# PCB_Schaltplan.net
KiCad netlist of a schematic drawn in EasyEDA
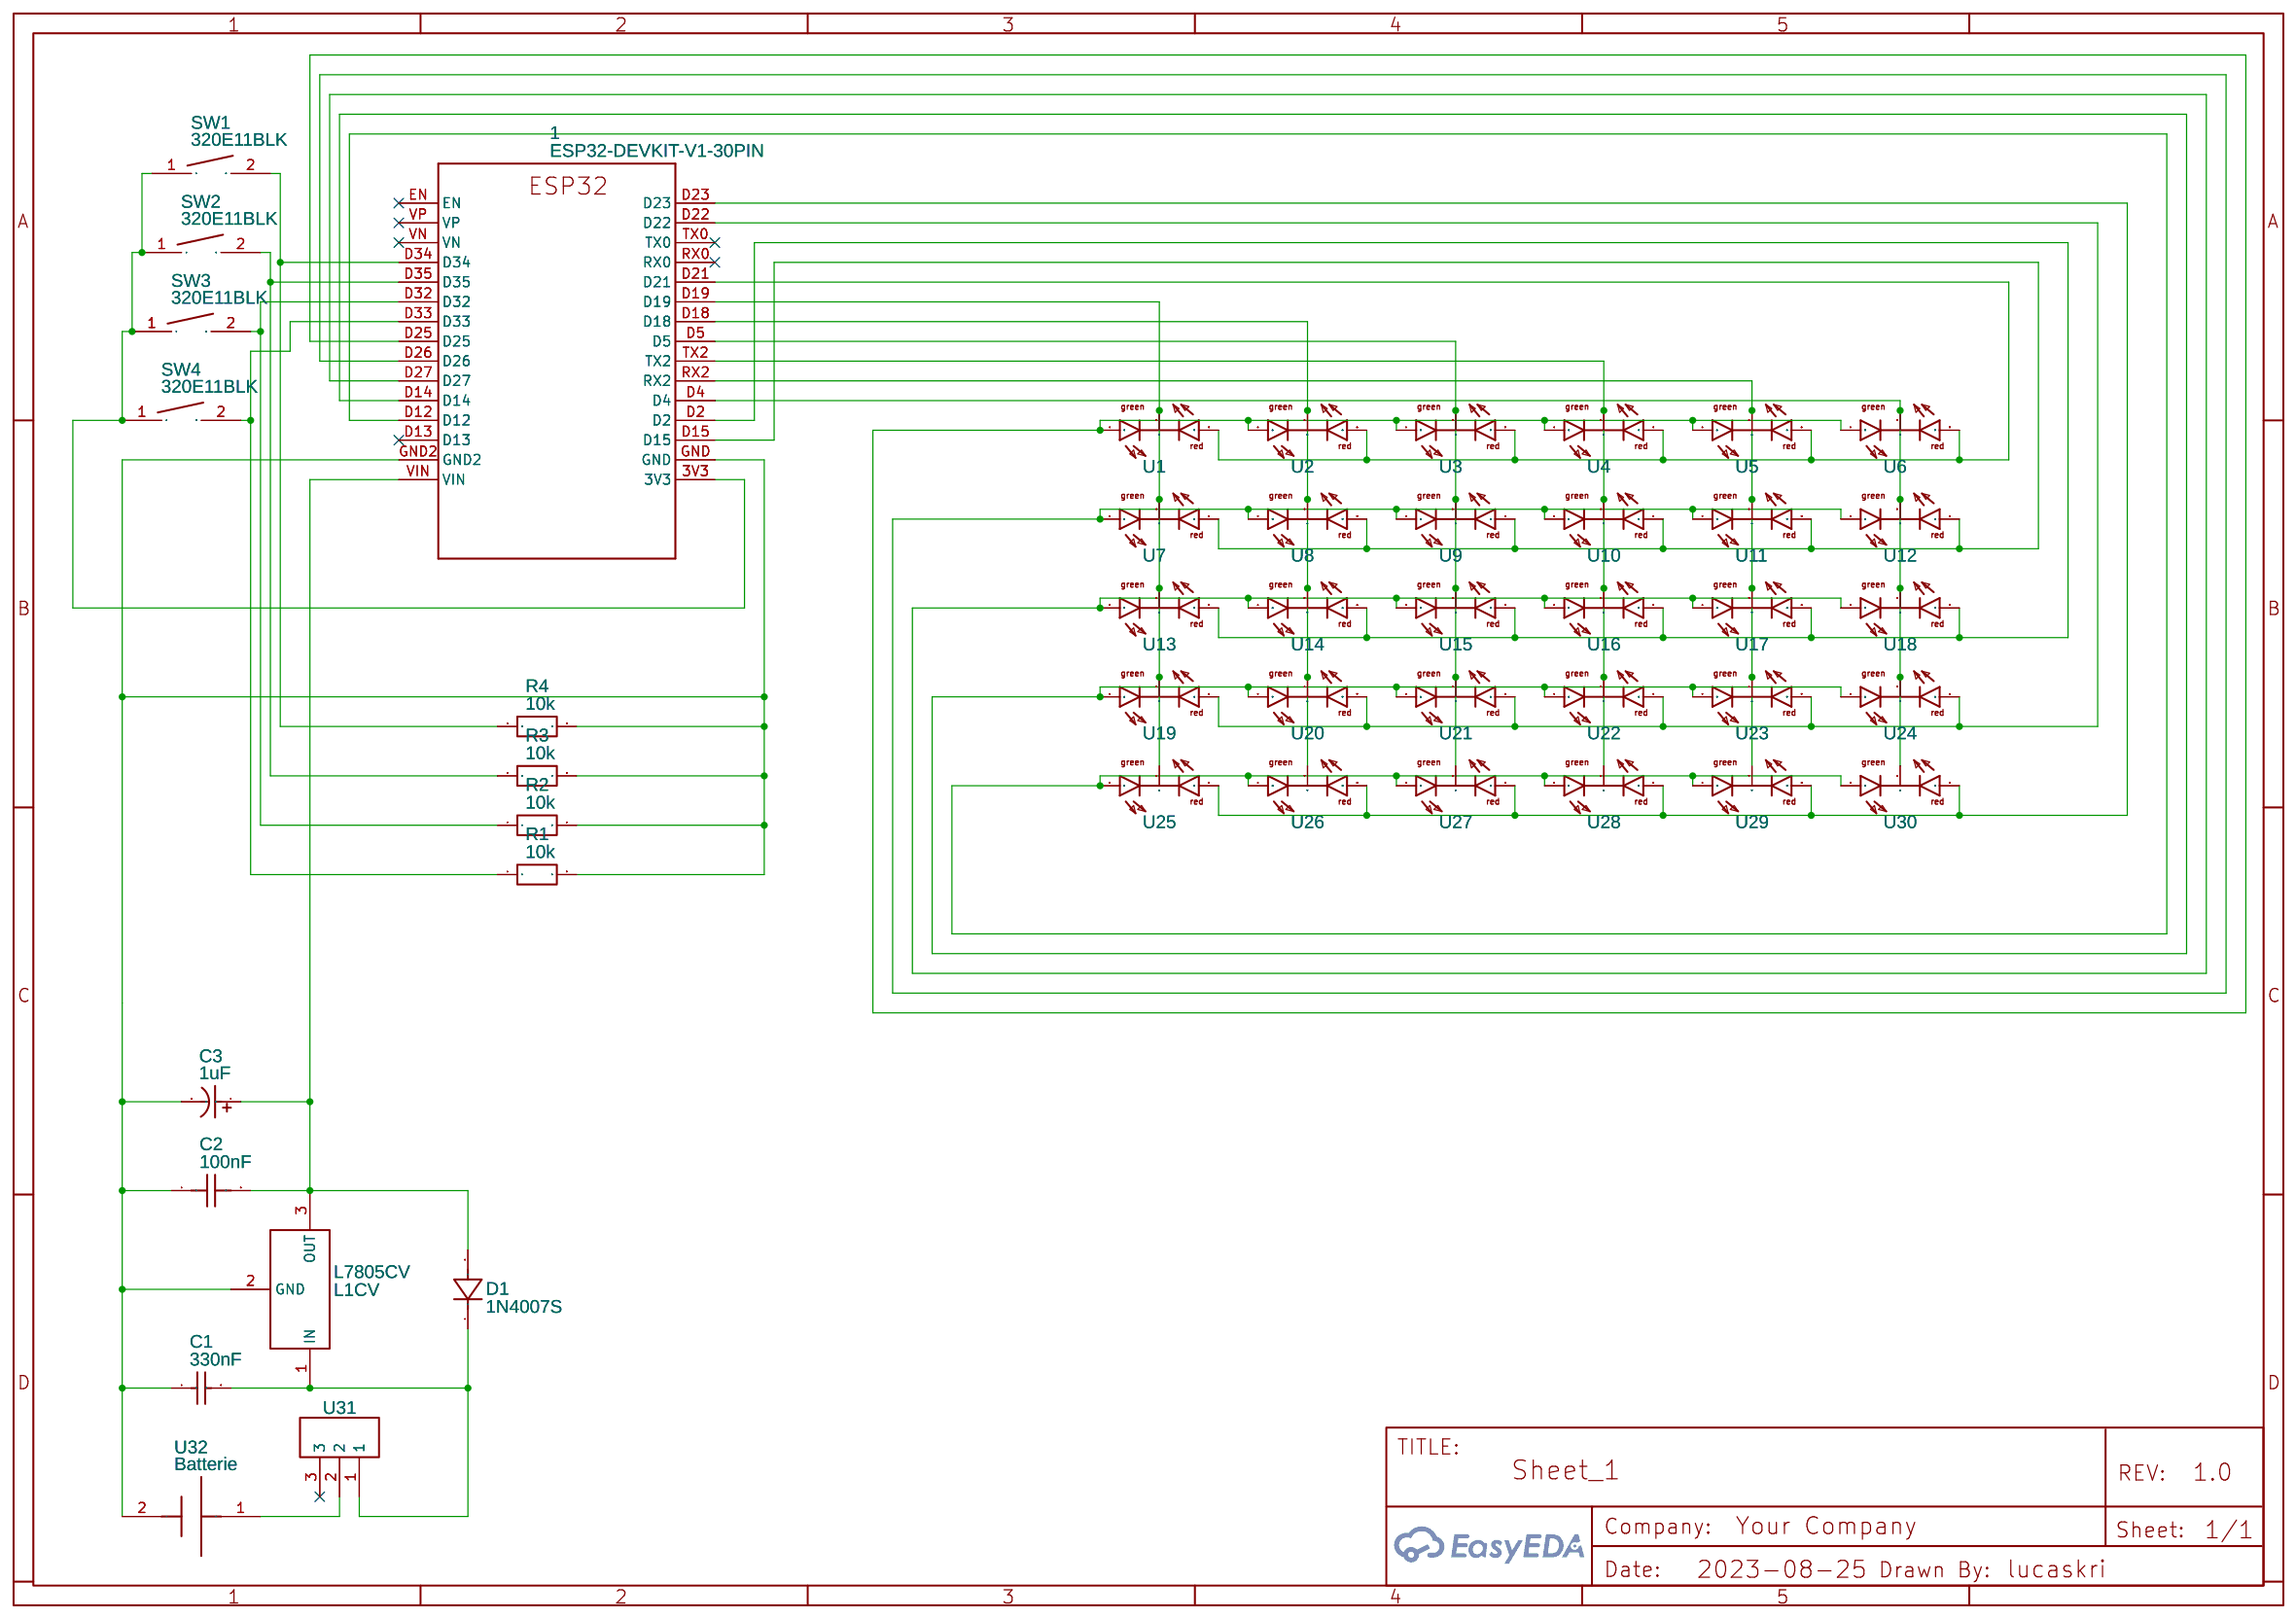
[diagram p0: schematic sheet]

(export (version "E")
  (design (tool "Eeschema 10.0.6"))
  (components
    (comp (ref "1") (value "ESP32-DEVKIT-V1-30PIN") (libsource (lib "") (part "ESP32-DEVKIT-V1-30PIN")))
    (comp (ref "C1")
      (value "330nF")
      (fields (field (name "Manufacturer Part") "CT4-1206Y334M500PF3") (field (name "Manufacturer") "FH(风华)"))
      (libsource (lib "") (part "CT4-1206Y334M500PF3"))
    )
    (comp (ref "C2")
      (value "100nF")
      (fields (field (name "Manufacturer Part") "B32529C0104M289") (field (name "Manufacturer") "TDK"))
      (libsource (lib "") (part "B32529C0104M289"))
    )
    (comp (ref "C3")
      (value "1uF")
      (fields
        (field (name "Manufacturer Part") "KF105M050C05RR0VH2FP0")
        (field (name "Manufacturer") "CX(承兴)")
      )
      (libsource (lib "") (part "1uF 50V 4*5"))
    )
    (comp (ref "D1")
      (value "1N4007S")
      (fields (field (name "Manufacturer") "星海"))
      (libsource (lib "") (part "1N4007S"))
    )
    (comp (ref "L1CV")
      (value "L7805CV")
      (fields (field (name "Manufacturer") "STMicroelectronics"))
      (libsource (lib "") (part "L7805CV"))
    )
    (comp (ref "R1") (value "10k") (libsource (lib "") (part "R_AXIAL-0.3_EU")))
    (comp (ref "R2") (value "10k") (libsource (lib "") (part "R_AXIAL-0.3_EU")))
    (comp (ref "R3") (value "10k") (libsource (lib "") (part "R_AXIAL-0.3_EU")))
    (comp (ref "R4") (value "10k") (libsource (lib "") (part "R_AXIAL-0.3_EU")))
    (comp (ref "SW1")
      (value "320E11BLK")
      (fields (field (name "Manufacturer") "E-Switch"))
      (libsource (lib "") (part "320E11BLK"))
    )
    (comp (ref "SW2")
      (value "320E11BLK")
      (fields (field (name "Manufacturer") "E-Switch"))
      (libsource (lib "") (part "320E11BLK"))
    )
    (comp (ref "SW3")
      (value "320E11BLK")
      (fields (field (name "Manufacturer") "E-Switch"))
      (libsource (lib "") (part "320E11BLK"))
    )
    (comp (ref "SW4")
      (value "320E11BLK")
      (fields (field (name "Manufacturer") "E-Switch"))
      (libsource (lib "") (part "320E11BLK"))
    )
    (comp (ref "U1") (value "NO") (libsource (lib "") (part "DUOLED-RG-C")))
    (comp (ref "U2") (value "NO") (libsource (lib "") (part "DUOLED-RG-C")))
    (comp (ref "U3") (value "NO") (libsource (lib "") (part "DUOLED-RG-C")))
    (comp (ref "U4") (value "NO") (libsource (lib "") (part "DUOLED-RG-C")))
    (comp (ref "U5") (value "NO") (libsource (lib "") (part "DUOLED-RG-C")))
    (comp (ref "U6") (value "NO") (libsource (lib "") (part "DUOLED-RG-C")))
    (comp (ref "U7") (value "NO") (libsource (lib "") (part "DUOLED-RG-C")))
    (comp (ref "U8") (value "NO") (libsource (lib "") (part "DUOLED-RG-C")))
    (comp (ref "U9") (value "NO") (libsource (lib "") (part "DUOLED-RG-C")))
    (comp (ref "U10") (value "NO") (libsource (lib "") (part "DUOLED-RG-C")))
    (comp (ref "U11") (value "NO") (libsource (lib "") (part "DUOLED-RG-C")))
    (comp (ref "U12") (value "NO") (libsource (lib "") (part "DUOLED-RG-C")))
    (comp (ref "U13") (value "NO") (libsource (lib "") (part "DUOLED-RG-C")))
    (comp (ref "U14") (value "NO") (libsource (lib "") (part "DUOLED-RG-C")))
    (comp (ref "U15") (value "NO") (libsource (lib "") (part "DUOLED-RG-C")))
    (comp (ref "U16") (value "NO") (libsource (lib "") (part "DUOLED-RG-C")))
    (comp (ref "U17") (value "NO") (libsource (lib "") (part "DUOLED-RG-C")))
    (comp (ref "U18") (value "NO") (libsource (lib "") (part "DUOLED-RG-C")))
    (comp (ref "U19") (value "NO") (libsource (lib "") (part "DUOLED-RG-C")))
    (comp (ref "U20") (value "NO") (libsource (lib "") (part "DUOLED-RG-C")))
    (comp (ref "U21") (value "NO") (libsource (lib "") (part "DUOLED-RG-C")))
    (comp (ref "U22") (value "NO") (libsource (lib "") (part "DUOLED-RG-C")))
    (comp (ref "U23") (value "NO") (libsource (lib "") (part "DUOLED-RG-C")))
    (comp (ref "U24") (value "NO") (libsource (lib "") (part "DUOLED-RG-C")))
    (comp (ref "U25") (value "NO") (libsource (lib "") (part "DUOLED-RG-C")))
    (comp (ref "U26") (value "NO") (libsource (lib "") (part "DUOLED-RG-C")))
    (comp (ref "U27") (value "NO") (libsource (lib "") (part "DUOLED-RG-C")))
    (comp (ref "U28") (value "NO") (libsource (lib "") (part "DUOLED-RG-C")))
    (comp (ref "U29") (value "NO") (libsource (lib "") (part "DUOLED-RG-C")))
    (comp (ref "U30") (value "NO") (libsource (lib "") (part "DUOLED-RG-C")))
    (comp (ref "U31") (value "NO") (libsource (lib "") (part "CSS-1201")))
    (comp (ref "U32") (value "Batterie") (libsource (lib "") (part "Batterie")))
  )
  (nets
    (net (code "1") (name "Net-(1-Pad3V3)") (class "Default")
      (node (ref "1") (pin "3V3") (pinfunction "3V3_3V3") (pintype "unspecified"))
      (node (ref "SW1") (pin "1") (pinfunction "1_1") (pintype "input"))
      (node (ref "SW2") (pin "1") (pinfunction "1_1") (pintype "input"))
      (node (ref "SW3") (pin "1") (pinfunction "1_1") (pintype "input"))
      (node (ref "SW4") (pin "1") (pinfunction "1_1") (pintype "input"))
    )
    (net (code "2") (name "Net-(1-PadD2)") (class "Default")
      (node (ref "1") (pin "D2") (pinfunction "D2_D2") (pintype "unspecified"))
      (node (ref "U13") (pin "AR") (pinfunction "AR_AR") (pintype "bidirectional"))
      (node (ref "U14") (pin "AR") (pinfunction "AR_AR") (pintype "bidirectional"))
      (node (ref "U15") (pin "AR") (pinfunction "AR_AR") (pintype "bidirectional"))
      (node (ref "U16") (pin "AR") (pinfunction "AR_AR") (pintype "bidirectional"))
      (node (ref "U17") (pin "AR") (pinfunction "AR_AR") (pintype "bidirectional"))
      (node (ref "U18") (pin "AR") (pinfunction "AR_AR") (pintype "bidirectional"))
    )
    (net (code "3") (name "Net-(1-PadD4)") (class "Default")
      (node (ref "1") (pin "D4") (pinfunction "D4_D4") (pintype "unspecified"))
      (node (ref "U12") (pin "C") (pinfunction "C_C") (pintype "bidirectional"))
      (node (ref "U18") (pin "C") (pinfunction "C_C") (pintype "bidirectional"))
      (node (ref "U24") (pin "C") (pinfunction "C_C") (pintype "bidirectional"))
      (node (ref "U30") (pin "C") (pinfunction "C_C") (pintype "bidirectional"))
      (node (ref "U6") (pin "C") (pinfunction "C_C") (pintype "bidirectional"))
    )
    (net (code "4") (name "Net-(1-PadD5)") (class "Default")
      (node (ref "1") (pin "D5") (pinfunction "D5_D5") (pintype "unspecified"))
      (node (ref "U15") (pin "C") (pinfunction "C_C") (pintype "bidirectional"))
      (node (ref "U21") (pin "C") (pinfunction "C_C") (pintype "bidirectional"))
      (node (ref "U27") (pin "C") (pinfunction "C_C") (pintype "bidirectional"))
      (node (ref "U3") (pin "C") (pinfunction "C_C") (pintype "bidirectional"))
      (node (ref "U9") (pin "C") (pinfunction "C_C") (pintype "bidirectional"))
    )
    (net (code "5") (name "Net-(1-PadD15)") (class "Default")
      (node (ref "1") (pin "D15") (pinfunction "D15_D15") (pintype "unspecified"))
      (node (ref "U10") (pin "AR") (pinfunction "AR_AR") (pintype "bidirectional"))
      (node (ref "U11") (pin "AR") (pinfunction "AR_AR") (pintype "bidirectional"))
      (node (ref "U12") (pin "AR") (pinfunction "AR_AR") (pintype "bidirectional"))
      (node (ref "U7") (pin "AR") (pinfunction "AR_AR") (pintype "bidirectional"))
      (node (ref "U8") (pin "AR") (pinfunction "AR_AR") (pintype "bidirectional"))
      (node (ref "U9") (pin "AR") (pinfunction "AR_AR") (pintype "bidirectional"))
    )
    (net (code "6") (name "Net-(1-PadD18)") (class "Default")
      (node (ref "1") (pin "D18") (pinfunction "D18_D18") (pintype "unspecified"))
      (node (ref "U14") (pin "C") (pinfunction "C_C") (pintype "bidirectional"))
      (node (ref "U2") (pin "C") (pinfunction "C_C") (pintype "bidirectional"))
      (node (ref "U20") (pin "C") (pinfunction "C_C") (pintype "bidirectional"))
      (node (ref "U26") (pin "C") (pinfunction "C_C") (pintype "bidirectional"))
      (node (ref "U8") (pin "C") (pinfunction "C_C") (pintype "bidirectional"))
    )
    (net (code "7") (name "Net-(1-PadD19)") (class "Default")
      (node (ref "1") (pin "D19") (pinfunction "D19_D19") (pintype "unspecified"))
      (node (ref "U1") (pin "C") (pinfunction "C_C") (pintype "bidirectional"))
      (node (ref "U13") (pin "C") (pinfunction "C_C") (pintype "bidirectional"))
      (node (ref "U19") (pin "C") (pinfunction "C_C") (pintype "bidirectional"))
      (node (ref "U25") (pin "C") (pinfunction "C_C") (pintype "bidirectional"))
      (node (ref "U7") (pin "C") (pinfunction "C_C") (pintype "bidirectional"))
    )
    (net (code "8") (name "Net-(1-PadD21)") (class "Default")
      (node (ref "1") (pin "D21") (pinfunction "D21_D21") (pintype "unspecified"))
      (node (ref "U1") (pin "AR") (pinfunction "AR_AR") (pintype "bidirectional"))
      (node (ref "U2") (pin "AR") (pinfunction "AR_AR") (pintype "bidirectional"))
      (node (ref "U3") (pin "AR") (pinfunction "AR_AR") (pintype "bidirectional"))
      (node (ref "U4") (pin "AR") (pinfunction "AR_AR") (pintype "bidirectional"))
      (node (ref "U5") (pin "AR") (pinfunction "AR_AR") (pintype "bidirectional"))
      (node (ref "U6") (pin "AR") (pinfunction "AR_AR") (pintype "bidirectional"))
    )
    (net (code "9") (name "Net-(1-PadD22)") (class "Default")
      (node (ref "1") (pin "D22") (pinfunction "D22_D22") (pintype "unspecified"))
      (node (ref "U19") (pin "AR") (pinfunction "AR_AR") (pintype "bidirectional"))
      (node (ref "U20") (pin "AR") (pinfunction "AR_AR") (pintype "bidirectional"))
      (node (ref "U21") (pin "AR") (pinfunction "AR_AR") (pintype "bidirectional"))
      (node (ref "U22") (pin "AR") (pinfunction "AR_AR") (pintype "bidirectional"))
      (node (ref "U23") (pin "AR") (pinfunction "AR_AR") (pintype "bidirectional"))
      (node (ref "U24") (pin "AR") (pinfunction "AR_AR") (pintype "bidirectional"))
    )
    (net (code "10") (name "Net-(1-PadD23)") (class "Default")
      (node (ref "1") (pin "D23") (pinfunction "D23_D23") (pintype "unspecified"))
      (node (ref "U25") (pin "AR") (pinfunction "AR_AR") (pintype "bidirectional"))
      (node (ref "U26") (pin "AR") (pinfunction "AR_AR") (pintype "bidirectional"))
      (node (ref "U27") (pin "AR") (pinfunction "AR_AR") (pintype "bidirectional"))
      (node (ref "U28") (pin "AR") (pinfunction "AR_AR") (pintype "bidirectional"))
      (node (ref "U29") (pin "AR") (pinfunction "AR_AR") (pintype "bidirectional"))
      (node (ref "U30") (pin "AR") (pinfunction "AR_AR") (pintype "bidirectional"))
    )
    (net (code "11") (name "Net-(1-PadD32)") (class "Default")
      (node (ref "1") (pin "D32") (pinfunction "D32_D32") (pintype "unspecified"))
      (node (ref "R2") (pin "1") (pinfunction "1_1") (pintype "unspecified"))
      (node (ref "SW3") (pin "2") (pinfunction "2_2") (pintype "input"))
    )
    (net (code "12") (name "Net-(1-PadD33)") (class "Default")
      (node (ref "1") (pin "D33") (pinfunction "D33_D33") (pintype "unspecified"))
      (node (ref "R1") (pin "1") (pinfunction "1_1") (pintype "unspecified"))
      (node (ref "SW4") (pin "2") (pinfunction "2_2") (pintype "input"))
    )
    (net (code "13") (name "Net-(1-PadD34)") (class "Default")
      (node (ref "1") (pin "D34") (pinfunction "D34_D34") (pintype "unspecified"))
      (node (ref "R4") (pin "1") (pinfunction "1_1") (pintype "unspecified"))
      (node (ref "SW1") (pin "2") (pinfunction "2_2") (pintype "input"))
    )
    (net (code "14") (name "Net-(1-PadD35)") (class "Default")
      (node (ref "1") (pin "D35") (pinfunction "D35_D35") (pintype "unspecified"))
      (node (ref "R3") (pin "1") (pinfunction "1_1") (pintype "unspecified"))
      (node (ref "SW2") (pin "2") (pinfunction "2_2") (pintype "input"))
    )
    (net (code "15") (name "Net-(1-PadRX2)") (class "Default")
      (node (ref "1") (pin "RX2") (pinfunction "RX2_RX2") (pintype "unspecified"))
      (node (ref "U11") (pin "C") (pinfunction "C_C") (pintype "bidirectional"))
      (node (ref "U17") (pin "C") (pinfunction "C_C") (pintype "bidirectional"))
      (node (ref "U23") (pin "C") (pinfunction "C_C") (pintype "bidirectional"))
      (node (ref "U29") (pin "C") (pinfunction "C_C") (pintype "bidirectional"))
      (node (ref "U5") (pin "C") (pinfunction "C_C") (pintype "bidirectional"))
    )
    (net (code "16") (name "Net-(1-PadTX2)") (class "Default")
      (node (ref "1") (pin "TX2") (pinfunction "TX2_TX2") (pintype "unspecified"))
      (node (ref "U10") (pin "C") (pinfunction "C_C") (pintype "bidirectional"))
      (node (ref "U16") (pin "C") (pinfunction "C_C") (pintype "bidirectional"))
      (node (ref "U22") (pin "C") (pinfunction "C_C") (pintype "bidirectional"))
      (node (ref "U28") (pin "C") (pinfunction "C_C") (pintype "bidirectional"))
      (node (ref "U4") (pin "C") (pinfunction "C_C") (pintype "bidirectional"))
    )
    (net (code "17") (name "Net-(D1-A)") (class "Default")
      (node (ref "1") (pin "VIN") (pinfunction "VIN_VIN") (pintype "unspecified"))
      (node (ref "C2") (pin "2") (pinfunction "2_2") (pintype "unspecified"))
      (node (ref "C3") (pin "1") (pinfunction "1_1") (pintype "input"))
      (node (ref "D1") (pin "2") (pinfunction "A_2") (pintype "unspecified"))
      (node (ref "L1CV") (pin "3") (pinfunction "OUT_3") (pintype "unspecified"))
    )
    (net (code "18") (name "Net-(D1-K)") (class "Default")
      (node (ref "C1") (pin "2") (pinfunction "2_2") (pintype "input"))
      (node (ref "D1") (pin "1") (pinfunction "K_1") (pintype "unspecified"))
      (node (ref "L1CV") (pin "1") (pinfunction "IN_1") (pintype "unspecified"))
      (node (ref "U31") (pin "1") (pinfunction "1_1") (pintype "unspecified"))
    )
    (net (code "19") (name "Net-(L1CV-GND)") (class "Default")
      (node (ref "1") (pin "GND") (pinfunction "GND_GND") (pintype "unspecified"))
      (node (ref "1") (pin "GND2") (pinfunction "GND2_GND2") (pintype "unspecified"))
      (node (ref "C1") (pin "1") (pinfunction "1_1") (pintype "input"))
      (node (ref "C2") (pin "1") (pinfunction "1_1") (pintype "unspecified"))
      (node (ref "C3") (pin "2") (pinfunction "2_2") (pintype "input"))
      (node (ref "L1CV") (pin "2") (pinfunction "GND_2") (pintype "unspecified"))
      (node (ref "R1") (pin "2") (pinfunction "2_2") (pintype "unspecified"))
      (node (ref "R2") (pin "2") (pinfunction "2_2") (pintype "unspecified"))
      (node (ref "R3") (pin "2") (pinfunction "2_2") (pintype "unspecified"))
      (node (ref "R4") (pin "2") (pinfunction "2_2") (pintype "unspecified"))
      (node (ref "U32") (pin "2") (pinfunction "-_2") (pintype "unspecified"))
    )
    (net (code "20") (name "Net-(U1-AG)") (class "Default")
      (node (ref "1") (pin "D25") (pinfunction "D25_D25") (pintype "unspecified"))
      (node (ref "U1") (pin "AX") (pinfunction "AG_AX") (pintype "bidirectional"))
      (node (ref "U2") (pin "AX") (pinfunction "AG_AX") (pintype "bidirectional"))
      (node (ref "U3") (pin "AX") (pinfunction "AG_AX") (pintype "bidirectional"))
      (node (ref "U4") (pin "AX") (pinfunction "AG_AX") (pintype "bidirectional"))
      (node (ref "U5") (pin "AX") (pinfunction "AG_AX") (pintype "bidirectional"))
      (node (ref "U6") (pin "AX") (pinfunction "AG_AX") (pintype "bidirectional"))
    )
    (net (code "21") (name "Net-(U10-AG)") (class "Default")
      (node (ref "1") (pin "D26") (pinfunction "D26_D26") (pintype "unspecified"))
      (node (ref "U10") (pin "AX") (pinfunction "AG_AX") (pintype "bidirectional"))
      (node (ref "U11") (pin "AX") (pinfunction "AG_AX") (pintype "bidirectional"))
      (node (ref "U12") (pin "AX") (pinfunction "AG_AX") (pintype "bidirectional"))
      (node (ref "U7") (pin "AX") (pinfunction "AG_AX") (pintype "bidirectional"))
      (node (ref "U8") (pin "AX") (pinfunction "AG_AX") (pintype "bidirectional"))
      (node (ref "U9") (pin "AX") (pinfunction "AG_AX") (pintype "bidirectional"))
    )
    (net (code "22") (name "Net-(U13-AG)") (class "Default")
      (node (ref "1") (pin "D27") (pinfunction "D27_D27") (pintype "unspecified"))
      (node (ref "U13") (pin "AX") (pinfunction "AG_AX") (pintype "bidirectional"))
      (node (ref "U14") (pin "AX") (pinfunction "AG_AX") (pintype "bidirectional"))
      (node (ref "U15") (pin "AX") (pinfunction "AG_AX") (pintype "bidirectional"))
      (node (ref "U16") (pin "AX") (pinfunction "AG_AX") (pintype "bidirectional"))
      (node (ref "U17") (pin "AX") (pinfunction "AG_AX") (pintype "bidirectional"))
      (node (ref "U18") (pin "AX") (pinfunction "AG_AX") (pintype "bidirectional"))
    )
    (net (code "23") (name "Net-(U19-AG)") (class "Default")
      (node (ref "1") (pin "D14") (pinfunction "D14_D14") (pintype "unspecified"))
      (node (ref "U19") (pin "AX") (pinfunction "AG_AX") (pintype "bidirectional"))
      (node (ref "U20") (pin "AX") (pinfunction "AG_AX") (pintype "bidirectional"))
      (node (ref "U21") (pin "AX") (pinfunction "AG_AX") (pintype "bidirectional"))
      (node (ref "U22") (pin "AX") (pinfunction "AG_AX") (pintype "bidirectional"))
      (node (ref "U23") (pin "AX") (pinfunction "AG_AX") (pintype "bidirectional"))
      (node (ref "U24") (pin "AX") (pinfunction "AG_AX") (pintype "bidirectional"))
    )
    (net (code "24") (name "Net-(U25-AG)") (class "Default")
      (node (ref "1") (pin "D12") (pinfunction "D12_D12") (pintype "unspecified"))
      (node (ref "U25") (pin "AX") (pinfunction "AG_AX") (pintype "bidirectional"))
      (node (ref "U26") (pin "AX") (pinfunction "AG_AX") (pintype "bidirectional"))
      (node (ref "U27") (pin "AX") (pinfunction "AG_AX") (pintype "bidirectional"))
      (node (ref "U28") (pin "AX") (pinfunction "AG_AX") (pintype "bidirectional"))
      (node (ref "U29") (pin "AX") (pinfunction "AG_AX") (pintype "bidirectional"))
      (node (ref "U30") (pin "AX") (pinfunction "AG_AX") (pintype "bidirectional"))
    )
    (net (code "25") (name "Net-(U32-+)") (class "Default")
      (node (ref "U31") (pin "2") (pinfunction "2_2") (pintype "unspecified"))
      (node (ref "U32") (pin "1") (pinfunction "+_1") (pintype "unspecified"))
    )
    (net (code "26") (name "unconnected-(1-PadD13)") (class "Default")
      (node (ref "1") (pin "D13") (pinfunction "D13_D13") (pintype "unspecified+no_connect"))
    )
    (net (code "27") (name "unconnected-(1-PadEN)") (class "Default")
      (node (ref "1") (pin "EN") (pinfunction "EN_EN") (pintype "unspecified+no_connect"))
    )
    (net (code "28") (name "unconnected-(1-PadRX0)") (class "Default")
      (node (ref "1") (pin "RX0") (pinfunction "RX0_RX0") (pintype "unspecified+no_connect"))
    )
    (net (code "29") (name "unconnected-(1-PadTX0)") (class "Default")
      (node (ref "1") (pin "TX0") (pinfunction "TX0_TX0") (pintype "unspecified+no_connect"))
    )
    (net (code "30") (name "unconnected-(1-PadVN)") (class "Default")
      (node (ref "1") (pin "VN") (pinfunction "VN_VN") (pintype "unspecified+no_connect"))
    )
    (net (code "31") (name "unconnected-(1-PadVP)") (class "Default")
      (node (ref "1") (pin "VP") (pinfunction "VP_VP") (pintype "unspecified+no_connect"))
    )
    (net (code "32") (name "unconnected-(U31-Pad3)") (class "Default")
      (node (ref "U31") (pin "3") (pinfunction "3_3") (pintype "unspecified+no_connect"))
    )
  )
)
